# Schematic.net
KiCad netlist of a schematic drawn in Altium Designer
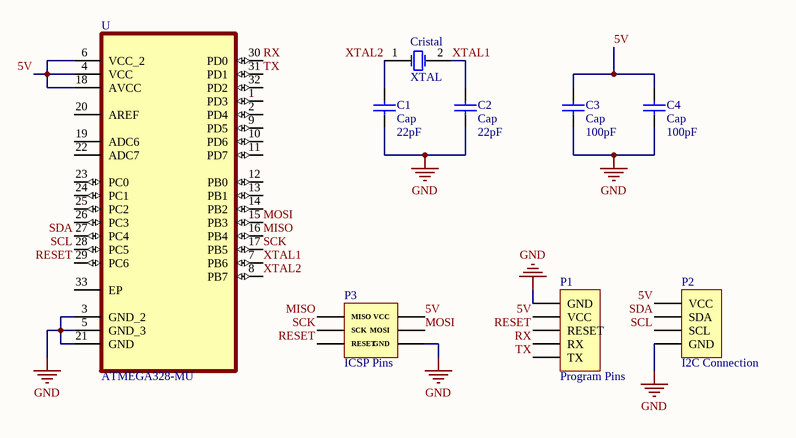
[diagram p0: Schematic.SchDoc]

(export (version "E")
  (design (tool "Eeschema 10.0.6"))
  (components
    (comp (ref "C1")
      (value "Cap")
      (footprint "RAD-0.3")
      (description "Capacitor")
      (fields (field (name "ALTIUM_VALUE") "22pF") (field (name "PUBLISHER") "Altium Limited"))
      (libsource (lib "Miscellaneous Devices") (part "Cap"))
    )
    (comp (ref "C2")
      (value "Cap")
      (footprint "RAD-0.3")
      (description "Capacitor")
      (fields (field (name "ALTIUM_VALUE") "22pF") (field (name "PUBLISHER") "Altium Limited"))
      (libsource (lib "Miscellaneous Devices") (part "Cap"))
    )
    (comp (ref "C3")
      (value "Cap")
      (footprint "RAD-0.3")
      (description "Capacitor")
      (fields (field (name "ALTIUM_VALUE") "100pF") (field (name "PUBLISHER") "Altium Limited"))
      (libsource (lib "Miscellaneous Devices") (part "Cap"))
    )
    (comp (ref "C4")
      (value "Cap")
      (footprint "RAD-0.3")
      (description "Capacitor")
      (fields (field (name "ALTIUM_VALUE") "100pF") (field (name "PUBLISHER") "Altium Limited"))
      (libsource (lib "Miscellaneous Devices") (part "Cap"))
    )
    (comp (ref "Cristal")
      (value "XTAL")
      (footprint "R38")
      (description "Crystal Oscillator")
      (fields (field (name "PUBLISHER") "Altium Limited"))
      (libsource (lib "Miscellaneous Devices") (part "XTAL"))
    )
    (comp (ref "P1")
      (value "Program Pins")
      (footprint "HDR1X5")
      (description "Header, 5-Pin")
      (fields (field (name "PUBLISHER") "Altium Limited"))
      (libsource (lib "Miscellaneous Connectors") (part "Header 5"))
    )
    (comp (ref "P2")
      (value "I2C Connection")
      (footprint "HDR1X4H")
      (description "Header, 4-Pin, Right Angle")
      (fields (field (name "PUBLISHER") "Altium Limited"))
      (libsource (lib "Miscellaneous Connectors") (part "Header 4H"))
    )
    (comp (ref "P3")
      (value "ICSP Pins")
      (footprint "HDR2X3")
      (description "Header, 3-Pin, Dual row")
      (fields (field (name "PUBLISHER") "Altium Limited"))
      (libsource (lib "Miscellaneous Connectors") (part "Header 3X2"))
    )
    (comp (ref "U")
      (value "ATMEGA328-MU")
      (footprint "QFN50P500X500X100-33N")
      (description "AVR AVRÂ® ATmega Microcontroller IC 8-Bit 20MHz 32KB _16K x 16_ FLASH 32-VQFN _5x5_")
      (fields (field (name "MF") "Microchip"))
      (libsource (lib "ATMEGA328-MU") (part "ATMEGA328-MU"))
    )
  )
  (nets
    (net (code "1") (name "/5V") (class "Default")
      (node (ref "C3") (pin "2") (pinfunction "2_2") (pintype "passive"))
      (node (ref "C4") (pin "2") (pinfunction "2_2") (pintype "passive"))
      (node (ref "P1") (pin "2") (pinfunction "VCC_2") (pintype "power_in"))
      (node (ref "P2") (pin "1") (pinfunction "VCC_1") (pintype "passive"))
      (node (ref "P3") (pin "2") (pinfunction "VCC_2") (pintype "power_in"))
      (node (ref "U") (pin "18") (pinfunction "AVCC_18") (pintype "power_in"))
      (node (ref "U") (pin "4") (pinfunction "VCC_4") (pintype "power_in"))
      (node (ref "U") (pin "6") (pinfunction "VCC_2_6") (pintype "power_in"))
    )
    (net (code "2") (name "/MISO") (class "Default")
      (node (ref "P3") (pin "1") (pinfunction "MISO_1") (pintype "passive"))
      (node (ref "U") (pin "16") (pinfunction "PB4_16") (pintype "bidirectional"))
    )
    (net (code "3") (name "/MOSI") (class "Default")
      (node (ref "P3") (pin "4") (pinfunction "MOSI_4") (pintype "passive"))
      (node (ref "U") (pin "15") (pinfunction "PB3_15") (pintype "bidirectional"))
    )
    (net (code "4") (name "/RESET") (class "Default")
      (node (ref "P1") (pin "3") (pinfunction "RESET_3") (pintype "passive"))
      (node (ref "P3") (pin "5") (pinfunction "RESET_5") (pintype "passive"))
      (node (ref "U") (pin "29") (pinfunction "PC6_29") (pintype "bidirectional"))
    )
    (net (code "5") (name "/RX") (class "Default")
      (node (ref "P1") (pin "4") (pinfunction "RX_4") (pintype "passive"))
      (node (ref "U") (pin "30") (pinfunction "PD0_30") (pintype "bidirectional"))
    )
    (net (code "6") (name "/SCK") (class "Default")
      (node (ref "P3") (pin "3") (pinfunction "SCK_3") (pintype "passive"))
      (node (ref "U") (pin "17") (pinfunction "PB5_17") (pintype "bidirectional"))
    )
    (net (code "7") (name "/SCL") (class "Default")
      (node (ref "P2") (pin "3") (pinfunction "SCL_3") (pintype "passive"))
      (node (ref "U") (pin "28") (pinfunction "PC5_28") (pintype "bidirectional"))
    )
    (net (code "8") (name "/SDA") (class "Default")
      (node (ref "P2") (pin "2") (pinfunction "SDA_2") (pintype "passive"))
      (node (ref "U") (pin "27") (pinfunction "PC4_27") (pintype "bidirectional"))
    )
    (net (code "9") (name "/TX") (class "Default")
      (node (ref "P1") (pin "5") (pinfunction "TX_5") (pintype "passive"))
      (node (ref "U") (pin "31") (pinfunction "PD1_31") (pintype "bidirectional"))
    )
    (net (code "10") (name "/XTAL1") (class "Default")
      (node (ref "C2") (pin "2") (pinfunction "2_2") (pintype "passive"))
      (node (ref "Cristal") (pin "2") (pinfunction "OSC2_2") (pintype "passive"))
      (node (ref "U") (pin "7") (pinfunction "PB6_7") (pintype "bidirectional"))
    )
    (net (code "11") (name "/XTAL2") (class "Default")
      (node (ref "C1") (pin "2") (pinfunction "2_2") (pintype "passive"))
      (node (ref "Cristal") (pin "1") (pinfunction "OSC1_1") (pintype "passive"))
      (node (ref "U") (pin "8") (pinfunction "PB7_8") (pintype "bidirectional"))
    )
    (net (code "12") (name "GND") (class "Default")
      (node (ref "C1") (pin "1") (pinfunction "1_1") (pintype "passive"))
      (node (ref "C2") (pin "1") (pinfunction "1_1") (pintype "passive"))
      (node (ref "C3") (pin "1") (pinfunction "1_1") (pintype "passive"))
      (node (ref "C4") (pin "1") (pinfunction "1_1") (pintype "passive"))
      (node (ref "P1") (pin "1") (pinfunction "GND_1") (pintype "power_in"))
      (node (ref "P2") (pin "4") (pinfunction "GND_4") (pintype "passive"))
      (node (ref "P3") (pin "6") (pinfunction "GND_6") (pintype "power_in"))
      (node (ref "U") (pin "21") (pinfunction "GND_21") (pintype "passive"))
      (node (ref "U") (pin "3") (pinfunction "GND_2_3") (pintype "passive"))
      (node (ref "U") (pin "5") (pinfunction "GND_3_5") (pintype "passive"))
    )
    (net (code "13") (name "unconnected-(U-ADC6-Pad19)") (class "Default")
      (node (ref "U") (pin "19") (pinfunction "ADC6_19") (pintype "passive"))
    )
    (net (code "14") (name "unconnected-(U-ADC7-Pad22)") (class "Default")
      (node (ref "U") (pin "22") (pinfunction "ADC7_22") (pintype "passive"))
    )
    (net (code "15") (name "unconnected-(U-AREF-Pad20)") (class "Default")
      (node (ref "U") (pin "20") (pinfunction "AREF_20") (pintype "passive"))
    )
    (net (code "16") (name "unconnected-(U-EP-Pad33)") (class "Default")
      (node (ref "U") (pin "33") (pinfunction "EP_33") (pintype "passive"))
    )
    (net (code "17") (name "unconnected-(U-PB0-Pad12)") (class "Default")
      (node (ref "U") (pin "12") (pinfunction "PB0_12") (pintype "bidirectional"))
    )
    (net (code "18") (name "unconnected-(U-PB1-Pad13)") (class "Default")
      (node (ref "U") (pin "13") (pinfunction "PB1_13") (pintype "bidirectional"))
    )
    (net (code "19") (name "unconnected-(U-PB2-Pad14)") (class "Default")
      (node (ref "U") (pin "14") (pinfunction "PB2_14") (pintype "bidirectional"))
    )
    (net (code "20") (name "unconnected-(U-PC0-Pad23)") (class "Default")
      (node (ref "U") (pin "23") (pinfunction "PC0_23") (pintype "bidirectional"))
    )
    (net (code "21") (name "unconnected-(U-PC1-Pad24)") (class "Default")
      (node (ref "U") (pin "24") (pinfunction "PC1_24") (pintype "bidirectional"))
    )
    (net (code "22") (name "unconnected-(U-PC2-Pad25)") (class "Default")
      (node (ref "U") (pin "25") (pinfunction "PC2_25") (pintype "bidirectional"))
    )
    (net (code "23") (name "unconnected-(U-PC3-Pad26)") (class "Default")
      (node (ref "U") (pin "26") (pinfunction "PC3_26") (pintype "bidirectional"))
    )
    (net (code "24") (name "unconnected-(U-PD2-Pad32)") (class "Default")
      (node (ref "U") (pin "32") (pinfunction "PD2_32") (pintype "bidirectional"))
    )
    (net (code "25") (name "unconnected-(U-PD3-Pad1)") (class "Default")
      (node (ref "U") (pin "1") (pinfunction "PD3_1") (pintype "bidirectional"))
    )
    (net (code "26") (name "unconnected-(U-PD4-Pad2)") (class "Default")
      (node (ref "U") (pin "2") (pinfunction "PD4_2") (pintype "bidirectional"))
    )
    (net (code "27") (name "unconnected-(U-PD5-Pad9)") (class "Default")
      (node (ref "U") (pin "9") (pinfunction "PD5_9") (pintype "bidirectional"))
    )
    (net (code "28") (name "unconnected-(U-PD6-Pad10)") (class "Default")
      (node (ref "U") (pin "10") (pinfunction "PD6_10") (pintype "bidirectional"))
    )
    (net (code "29") (name "unconnected-(U-PD7-Pad11)") (class "Default")
      (node (ref "U") (pin "11") (pinfunction "PD7_11") (pintype "bidirectional"))
    )
  )
)
